# LORA.net
KiCad netlist of a schematic drawn in Altium Designer
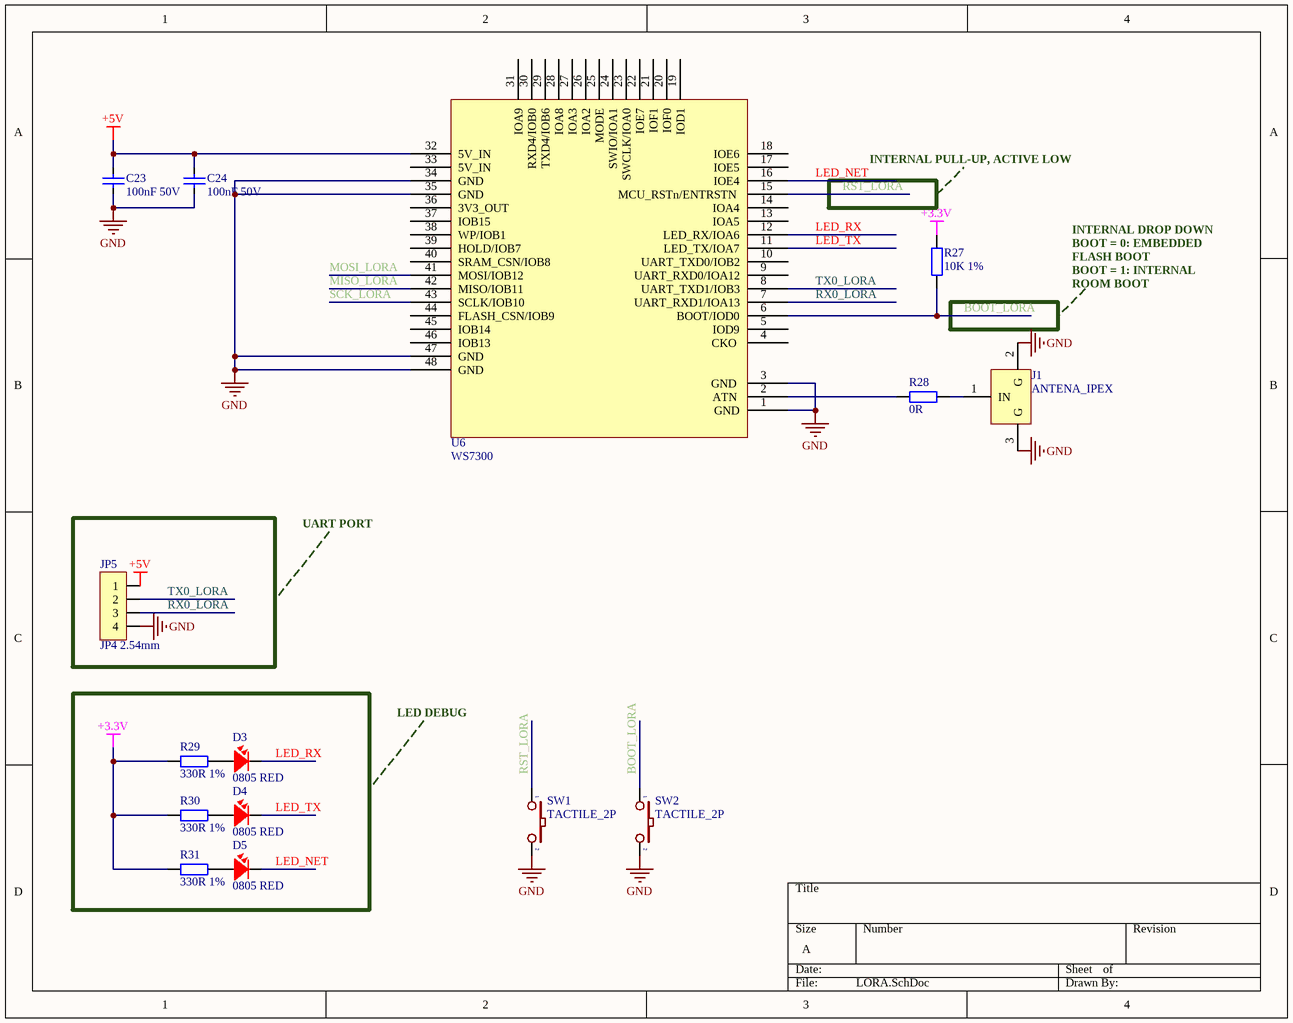
[diagram p0: LORA.SchDoc]

(export (version "E")
  (design (tool "Eeschema 10.0.6"))
  (components
    (comp (ref "C23")
      (value "100nF 50V")
      (footprint "CAP_SMD_0805")
      (description "0.1 µF ±10% 50V Ceramic Capacitor X7R 0805 (2012 Metric)")
      (fields
        (field (name "MANUFACTURER") "YAGEO")
        (field (name "MANUFACTURE PART NUMBER") "CC0805KRX7R9BB104")
      )
      (libsource (lib "Nhatkhongbuon") (part "C0805_MLCC_100nF_50V"))
    )
    (comp (ref "C24")
      (value "100nF 50V")
      (footprint "CAP_SMD_0805")
      (description "0.1 µF ±10% 50V Ceramic Capacitor X7R 0805 (2012 Metric)")
      (fields
        (field (name "MANUFACTURER") "YAGEO")
        (field (name "MANUFACTURE PART NUMBER") "CC0805KRX7R9BB104")
      )
      (libsource (lib "Nhatkhongbuon") (part "C0805_MLCC_100nF_50V"))
    )
    (comp (ref "D3")
      (value "0805 RED")
      (footprint "LED-0805-Red")
      (description "Red 625nm LED Indication - Discrete 2V 0805 (2012 Metric)")
      (fields
        (field (name "MANUFACTURER") "Würth Elektronik")
        (field (name "MANUFACTURE PART NUMBER") "150080RS75000")
      )
      (libsource (lib "Nhatkhongbuon") (part "LED_0805_RED"))
    )
    (comp (ref "D4")
      (value "0805 RED")
      (footprint "LED-0805-Red")
      (description "Red 625nm LED Indication - Discrete 2V 0805 (2012 Metric)")
      (fields
        (field (name "MANUFACTURER") "Würth Elektronik")
        (field (name "MANUFACTURE PART NUMBER") "150080RS75000")
      )
      (libsource (lib "Nhatkhongbuon") (part "LED_0805_RED"))
    )
    (comp (ref "D5")
      (value "0805 RED")
      (footprint "LED-0805-Red")
      (description "Red 625nm LED Indication - Discrete 2V 0805 (2012 Metric)")
      (fields
        (field (name "MANUFACTURER") "Würth Elektronik")
        (field (name "MANUFACTURE PART NUMBER") "150080RS75000")
      )
      (libsource (lib "Nhatkhongbuon") (part "LED_0805_RED"))
    )
    (comp (ref "J1")
      (value "ANTENA_IPEX")
      (footprint "IPEX")
      (description "U.FL (UMCC), IPEX MHFI Connector Receptacle, Male Pin Surface Mount Solder")
      (fields (field (name "MANUFACTURER") "I-PEX") (field (name "MANUFACTURE PART NUMBER") "20279-001E-03"))
      (libsource (lib "Nhatkhongbuon") (part "ANTENA_IPEX"))
    )
    (comp (ref "JP5")
      (value "JP4 2.54mm")
      (footprint "JP4_M")
      (description "Connector Header Through Hole 4 position 0.100\" (2.54mm)")
      (fields
        (field (name "MANUFACTURER") "Würth Elektronik")
        (field (name "MANUFACTURE PART NUMBER") "61300411121")
      )
      (libsource (lib "Nhatkhongbuon") (part "JP4M"))
    )
    (comp (ref "R27")
      (value "10K 1%")
      (footprint "RES_SMD_0805")
      (description "10 kOhms ±1% 0.125W, 1/8W Chip Resistor 0805 (2012 Metric) Moisture Resistant Thick Film")
      (fields
        (field (name "MANUFACTURER") "YAGEO")
        (field (name "MANUFACTURE PART NUMBER") "RC0805FR-0710KL")
      )
      (libsource (lib "Nhatkhongbuon") (part "R0805_10K"))
    )
    (comp (ref "R28")
      (value "0R")
      (footprint "RES_SMD_0805")
      (description "0 Ohms Jumper Chip Resistor 0805 (2012 Metric) Automotive AEC-Q200 Thick Film")
      (fields
        (field (name "MANUFACTURER") "Vishay Dale")
        (field (name "MANUFACTURE PART NUMBER") "CRCW08050000Z0EA")
      )
      (libsource (lib "Nhatkhongbuon") (part "R0805_0R"))
    )
    (comp (ref "R29")
      (value "330R 1%")
      (footprint "RES_SMD_0805")
      (description "330 Ohms ±1% 0.125W, 1/8W Chip Resistor 0805 (2012 Metric) Automotive AEC-Q200 Thick Film")
      (fields
        (field (name "MANUFACTURER") "Stackpole Electronics Inc")
        (field (name "MANUFACTURE PART NUMBER") "RMCF0805FT330R")
      )
      (libsource (lib "Nhatkhongbuon") (part "R0805_330R"))
    )
    (comp (ref "R30")
      (value "330R 1%")
      (footprint "RES_SMD_0805")
      (description "330 Ohms ±1% 0.125W, 1/8W Chip Resistor 0805 (2012 Metric) Automotive AEC-Q200 Thick Film")
      (fields
        (field (name "MANUFACTURER") "Stackpole Electronics Inc")
        (field (name "MANUFACTURE PART NUMBER") "RMCF0805FT330R")
      )
      (libsource (lib "Nhatkhongbuon") (part "R0805_330R"))
    )
    (comp (ref "R31")
      (value "330R 1%")
      (footprint "RES_SMD_0805")
      (description "330 Ohms ±1% 0.125W, 1/8W Chip Resistor 0805 (2012 Metric) Automotive AEC-Q200 Thick Film")
      (fields
        (field (name "MANUFACTURER") "Stackpole Electronics Inc")
        (field (name "MANUFACTURE PART NUMBER") "RMCF0805FT330R")
      )
      (libsource (lib "Nhatkhongbuon") (part "R0805_330R"))
    )
    (comp (ref "SW1")
      (value "TACTILE_2P")
      (footprint "C&K BUTTON 2P")
      (description "Tactile Switch SPST-NO Top Actuated Surface Mount")
      (fields
        (field (name "MANUFACTURER") "C&K")
        (field (name "MANUFACTURE PART NUMBER") "PTS636 SM43 SMTR LFS")
      )
      (libsource (lib "Nhatkhongbuon") (part "SWITCH_TACTILE_2P"))
    )
    (comp (ref "SW2")
      (value "TACTILE_2P")
      (footprint "C&K BUTTON 2P")
      (description "Tactile Switch SPST-NO Top Actuated Surface Mount")
      (fields
        (field (name "MANUFACTURER") "C&K")
        (field (name "MANUFACTURE PART NUMBER") "PTS636 SM43 SMTR LFS")
      )
      (libsource (lib "Nhatkhongbuon") (part "SWITCH_TACTILE_2P"))
    )
    (comp (ref "U6")
      (value "WS7300")
      (footprint "WS7300-S")
      (description "Wi-SUN wireless communication modules based on the VC7300BU chip from Lireda")
      (fields (field (name "MANUFACTURER") "Lireda"))
      (libsource (lib "Nhatkhongbuon") (part "WS7300"))
    )
  )
  (nets
    (net (code "1") (name "+3.3V") (class "Default")
      (node (ref "R27") (pin "2") (pinfunction "2_2") (pintype "passive"))
      (node (ref "R29") (pin "1") (pinfunction "1_1") (pintype "passive"))
      (node (ref "R30") (pin "1") (pinfunction "1_1") (pintype "passive"))
      (node (ref "R31") (pin "1") (pinfunction "1_1") (pintype "passive"))
    )
    (net (code "2") (name "+5V") (class "Default")
      (node (ref "C23") (pin "2") (pinfunction "2_2") (pintype "passive"))
      (node (ref "C24") (pin "2") (pinfunction "2_2") (pintype "passive"))
      (node (ref "JP5") (pin "1") (pinfunction "1_1") (pintype "passive"))
      (node (ref "U6") (pin "32") (pinfunction "5V_IN_32") (pintype "passive"))
    )
    (net (code "3") (name "/BOOT_LORA") (class "Default")
      (node (ref "R27") (pin "1") (pinfunction "1_1") (pintype "passive"))
      (node (ref "SW2") (pin "1") (pinfunction "1_1") (pintype "passive"))
      (node (ref "U6") (pin "6") (pinfunction "BOOT/IOD0_6") (pintype "passive"))
    )
    (net (code "4") (name "/LED_NET") (class "Default")
      (node (ref "D5") (pin "2") (pinfunction "2_2") (pintype "passive"))
      (node (ref "U6") (pin "16") (pinfunction "IOE4_16") (pintype "passive"))
    )
    (net (code "5") (name "/LED_RX") (class "Default")
      (node (ref "D3") (pin "2") (pinfunction "2_2") (pintype "passive"))
      (node (ref "U6") (pin "12") (pinfunction "LED_RX/IOA6_12") (pintype "passive"))
    )
    (net (code "6") (name "/LED_TX") (class "Default")
      (node (ref "D4") (pin "2") (pinfunction "2_2") (pintype "passive"))
      (node (ref "U6") (pin "11") (pinfunction "LED_TX/IOA7_11") (pintype "passive"))
    )
    (net (code "7") (name "/MISO_LORA") (class "Default")
      (node (ref "U6") (pin "42") (pinfunction "MISO/IOB11_42") (pintype "passive"))
    )
    (net (code "8") (name "/MOSI_LORA") (class "Default")
      (node (ref "U6") (pin "41") (pinfunction "MOSI/IOB12_41") (pintype "passive"))
    )
    (net (code "9") (name "/RST_LORA") (class "Default")
      (node (ref "SW1") (pin "1") (pinfunction "1_1") (pintype "passive"))
      (node (ref "U6") (pin "15") (pinfunction "MCU_RSTn/ENTRSTN_15") (pintype "passive"))
    )
    (net (code "10") (name "/RX0_LORA") (class "Default")
      (node (ref "JP5") (pin "3") (pinfunction "3_3") (pintype "passive"))
      (node (ref "U6") (pin "7") (pinfunction "UART_RXD1/IOA13_7") (pintype "passive"))
    )
    (net (code "11") (name "/SCK_LORA") (class "Default")
      (node (ref "U6") (pin "43") (pinfunction "SCLK/IOB10_43") (pintype "passive"))
    )
    (net (code "12") (name "/TX0_LORA") (class "Default")
      (node (ref "JP5") (pin "2") (pinfunction "2_2") (pintype "passive"))
      (node (ref "U6") (pin "8") (pinfunction "UART_TXD1/IOB3_8") (pintype "passive"))
    )
    (net (code "13") (name "GND") (class "Default")
      (node (ref "C23") (pin "1") (pinfunction "1_1") (pintype "passive"))
      (node (ref "C24") (pin "1") (pinfunction "1_1") (pintype "passive"))
      (node (ref "J1") (pin "2") (pinfunction "G_2") (pintype "passive"))
      (node (ref "J1") (pin "3") (pinfunction "G_3") (pintype "passive"))
      (node (ref "JP5") (pin "4") (pinfunction "4_4") (pintype "passive"))
      (node (ref "SW1") (pin "2") (pinfunction "2_2") (pintype "passive"))
      (node (ref "SW2") (pin "2") (pinfunction "2_2") (pintype "passive"))
      (node (ref "U6") (pin "1") (pinfunction "GND_1") (pintype "passive"))
      (node (ref "U6") (pin "3") (pinfunction "GND_3") (pintype "passive"))
      (node (ref "U6") (pin "34") (pinfunction "GND_34") (pintype "passive"))
      (node (ref "U6") (pin "35") (pinfunction "GND_35") (pintype "passive"))
      (node (ref "U6") (pin "47") (pinfunction "GND_47") (pintype "passive"))
      (node (ref "U6") (pin "48") (pinfunction "GND_48") (pintype "passive"))
    )
    (net (code "14") (name "Net-(D3-Pad1)") (class "Default")
      (node (ref "D3") (pin "1") (pinfunction "1_1") (pintype "passive"))
      (node (ref "R29") (pin "2") (pinfunction "2_2") (pintype "passive"))
    )
    (net (code "15") (name "Net-(D4-Pad1)") (class "Default")
      (node (ref "D4") (pin "1") (pinfunction "1_1") (pintype "passive"))
      (node (ref "R30") (pin "2") (pinfunction "2_2") (pintype "passive"))
    )
    (net (code "16") (name "Net-(D5-Pad1)") (class "Default")
      (node (ref "D5") (pin "1") (pinfunction "1_1") (pintype "passive"))
      (node (ref "R31") (pin "2") (pinfunction "2_2") (pintype "passive"))
    )
    (net (code "17") (name "Net-(J1-IN)") (class "Default")
      (node (ref "J1") (pin "1") (pinfunction "IN_1") (pintype "passive"))
      (node (ref "R28") (pin "2") (pinfunction "2_2") (pintype "passive"))
    )
    (net (code "18") (name "Net-(U6-ATN)") (class "Default")
      (node (ref "R28") (pin "1") (pinfunction "1_1") (pintype "passive"))
      (node (ref "U6") (pin "2") (pinfunction "ATN_2") (pintype "passive"))
    )
    (net (code "19") (name "unconnected-(U6-3V3_OUT-Pad36)") (class "Default")
      (node (ref "U6") (pin "36") (pinfunction "3V3_OUT_36") (pintype "passive"))
    )
    (net (code "20") (name "unconnected-(U6-5V_IN-Pad33)") (class "Default")
      (node (ref "U6") (pin "33") (pinfunction "5V_IN_33") (pintype "passive"))
    )
    (net (code "21") (name "unconnected-(U6-CKO-Pad4)") (class "Default")
      (node (ref "U6") (pin "4") (pinfunction "CKO_4") (pintype "passive"))
    )
    (net (code "22") (name "unconnected-(U6-FLASH_CSN{slash}IOB9-Pad44)") (class "Default")
      (node (ref "U6") (pin "44") (pinfunction "FLASH_CSN/IOB9_44") (pintype "passive"))
    )
    (net (code "23") (name "unconnected-(U6-HOLD{slash}IOB7-Pad39)") (class "Default")
      (node (ref "U6") (pin "39") (pinfunction "HOLD/IOB7_39") (pintype "passive"))
    )
    (net (code "24") (name "unconnected-(U6-IOA2-Pad26)") (class "Default")
      (node (ref "U6") (pin "26") (pinfunction "IOA2_26") (pintype "passive"))
    )
    (net (code "25") (name "unconnected-(U6-IOA3-Pad27)") (class "Default")
      (node (ref "U6") (pin "27") (pinfunction "IOA3_27") (pintype "passive"))
    )
    (net (code "26") (name "unconnected-(U6-IOA4-Pad14)") (class "Default")
      (node (ref "U6") (pin "14") (pinfunction "IOA4_14") (pintype "passive"))
    )
    (net (code "27") (name "unconnected-(U6-IOA5-Pad13)") (class "Default")
      (node (ref "U6") (pin "13") (pinfunction "IOA5_13") (pintype "passive"))
    )
    (net (code "28") (name "unconnected-(U6-IOA8-Pad28)") (class "Default")
      (node (ref "U6") (pin "28") (pinfunction "IOA8_28") (pintype "passive"))
    )
    (net (code "29") (name "unconnected-(U6-IOA9-Pad31)") (class "Default")
      (node (ref "U6") (pin "31") (pinfunction "IOA9_31") (pintype "passive"))
    )
    (net (code "30") (name "unconnected-(U6-IOB13-Pad46)") (class "Default")
      (node (ref "U6") (pin "46") (pinfunction "IOB13_46") (pintype "passive"))
    )
    (net (code "31") (name "unconnected-(U6-IOB14-Pad45)") (class "Default")
      (node (ref "U6") (pin "45") (pinfunction "IOB14_45") (pintype "passive"))
    )
    (net (code "32") (name "unconnected-(U6-IOB15-Pad37)") (class "Default")
      (node (ref "U6") (pin "37") (pinfunction "IOB15_37") (pintype "passive"))
    )
    (net (code "33") (name "unconnected-(U6-IOD1-Pad19)") (class "Default")
      (node (ref "U6") (pin "19") (pinfunction "IOD1_19") (pintype "passive"))
    )
    (net (code "34") (name "unconnected-(U6-IOD9-Pad5)") (class "Default")
      (node (ref "U6") (pin "5") (pinfunction "IOD9_5") (pintype "passive"))
    )
    (net (code "35") (name "unconnected-(U6-IOE5-Pad17)") (class "Default")
      (node (ref "U6") (pin "17") (pinfunction "IOE5_17") (pintype "passive"))
    )
    (net (code "36") (name "unconnected-(U6-IOE6-Pad18)") (class "Default")
      (node (ref "U6") (pin "18") (pinfunction "IOE6_18") (pintype "passive"))
    )
    (net (code "37") (name "unconnected-(U6-IOE7-Pad22)") (class "Default")
      (node (ref "U6") (pin "22") (pinfunction "IOE7_22") (pintype "passive"))
    )
    (net (code "38") (name "unconnected-(U6-IOF0-Pad20)") (class "Default")
      (node (ref "U6") (pin "20") (pinfunction "IOF0_20") (pintype "passive"))
    )
    (net (code "39") (name "unconnected-(U6-IOF1-Pad21)") (class "Default")
      (node (ref "U6") (pin "21") (pinfunction "IOF1_21") (pintype "passive"))
    )
    (net (code "40") (name "unconnected-(U6-MODE-Pad25)") (class "Default")
      (node (ref "U6") (pin "25") (pinfunction "MODE_25") (pintype "passive"))
    )
    (net (code "41") (name "unconnected-(U6-RXD4{slash}IOB0-Pad30)") (class "Default")
      (node (ref "U6") (pin "30") (pinfunction "RXD4/IOB0_30") (pintype "passive"))
    )
    (net (code "42") (name "unconnected-(U6-SRAM_CSN{slash}IOB8-Pad40)") (class "Default")
      (node (ref "U6") (pin "40") (pinfunction "SRAM_CSN/IOB8_40") (pintype "passive"))
    )
    (net (code "43") (name "unconnected-(U6-SWCLK{slash}IOA0-Pad23)") (class "Default")
      (node (ref "U6") (pin "23") (pinfunction "SWCLK/IOA0_23") (pintype "passive"))
    )
    (net (code "44") (name "unconnected-(U6-SWIO{slash}IOA1-Pad24)") (class "Default")
      (node (ref "U6") (pin "24") (pinfunction "SWIO/IOA1_24") (pintype "passive"))
    )
    (net (code "45") (name "unconnected-(U6-TXD4{slash}IOB6-Pad29)") (class "Default")
      (node (ref "U6") (pin "29") (pinfunction "TXD4/IOB6_29") (pintype "passive"))
    )
    (net (code "46") (name "unconnected-(U6-UART_RXD0{slash}IOA12-Pad9)") (class "Default")
      (node (ref "U6") (pin "9") (pinfunction "UART_RXD0/IOA12_9") (pintype "passive"))
    )
    (net (code "47") (name "unconnected-(U6-UART_TXD0{slash}IOB2-Pad10)") (class "Default")
      (node (ref "U6") (pin "10") (pinfunction "UART_TXD0/IOB2_10") (pintype "passive"))
    )
    (net (code "48") (name "unconnected-(U6-WP{slash}IOB1-Pad38)") (class "Default")
      (node (ref "U6") (pin "38") (pinfunction "WP/IOB1_38") (pintype "passive"))
    )
  )
)
